# BMA253_Triaxial_Acceleration_Sensor.net
KiCad netlist of a schematic drawn in Altium Designer
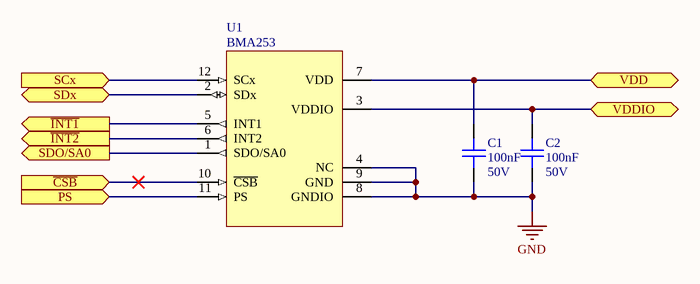
[diagram p0: BMA253_Triaxial_Acceleration_Sensor.SchDoc]

(export (version "E")
  (design (tool "Eeschema 10.0.6"))
  (components
    (comp (ref "C1")
      (value "CAP CER 0.1UF 50V X7R 0402")
      (footprint "C0402")
      (description "0.1µF ±10% 50V Ceramic Capacitor X7R 0402 (1005 Metric)")
      (fields
        (field (name "MANUFACTURER PART NUMBER") "CGA2B3X7R1H104K050BB")
        (field (name "MANUFACTURER") "TDK")
        (field (name "CAPACITANCE") "100nF")
        (field (name "VOLTAGE") "50V")
      )
      (libsource (lib "capacitors_smd") (part "CAP CER 0.1UF 50V X7R 0402"))
    )
    (comp (ref "C2")
      (value "CAP CER 0.1UF 50V X7R 0402")
      (footprint "C0402")
      (description "0.1µF ±10% 50V Ceramic Capacitor X7R 0402 (1005 Metric)")
      (fields
        (field (name "MANUFACTURER PART NUMBER") "CGA2B3X7R1H104K050BB")
        (field (name "MANUFACTURER") "TDK")
        (field (name "CAPACITANCE") "100nF")
        (field (name "VOLTAGE") "50V")
      )
      (libsource (lib "capacitors_smd") (part "CAP CER 0.1UF 50V X7R 0402"))
    )
    (comp (ref "U1")
      (value "BMA253")
      (footprint "LGA12C50P4X4_200X200X100")
      (description "Accelerometer X, Y, Z Axis ±2g, 4g, 8g, 16g 8Hz ~ 1kHz 12-LGA (2x2)")
      (fields (field (name "MANUFACTURER") "Bosch Sensortec"))
      (libsource (lib "BLDC_Motor_Driver") (part "IC BMA253 ACCEL 2-16G I2C/SPI 12LGA"))
    )
  )
  (nets
    (net (code "1") (name "/CSB") (class "Default")
      (node (ref "U1") (pin "10") (pinfunction "CSB_10") (pintype "input"))
    )
    (net (code "2") (name "/INT1") (class "Default")
      (node (ref "U1") (pin "5") (pinfunction "INT1_5") (pintype "output"))
    )
    (net (code "3") (name "/INT2") (class "Default")
      (node (ref "U1") (pin "6") (pinfunction "INT2_6") (pintype "output"))
    )
    (net (code "4") (name "/PS") (class "Default")
      (node (ref "U1") (pin "11") (pinfunction "PS_11") (pintype "input"))
    )
    (net (code "5") (name "/SCx") (class "Default")
      (node (ref "U1") (pin "12") (pinfunction "SCx_12") (pintype "input"))
    )
    (net (code "6") (name "/SDO{slash}SA0") (class "Default")
      (node (ref "U1") (pin "1") (pinfunction "SDO/SA0_1") (pintype "output"))
    )
    (net (code "7") (name "/SDx") (class "Default")
      (node (ref "U1") (pin "2") (pinfunction "SDx_2") (pintype "bidirectional"))
    )
    (net (code "8") (name "/VDD") (class "Default")
      (node (ref "C1") (pin "2") (pinfunction "2_2") (pintype "passive"))
      (node (ref "U1") (pin "7") (pinfunction "VDD_7") (pintype "power_in"))
    )
    (net (code "9") (name "/VDDIO") (class "Default")
      (node (ref "C2") (pin "1") (pinfunction "1_1") (pintype "passive"))
      (node (ref "U1") (pin "3") (pinfunction "VDDIO_3") (pintype "power_in"))
    )
    (net (code "10") (name "GND") (class "Default")
      (node (ref "C1") (pin "1") (pinfunction "1_1") (pintype "passive"))
      (node (ref "C2") (pin "2") (pinfunction "2_2") (pintype "passive"))
      (node (ref "U1") (pin "4") (pinfunction "NC_4") (pintype "passive"))
      (node (ref "U1") (pin "8") (pinfunction "GNDIO_8") (pintype "power_in"))
      (node (ref "U1") (pin "9") (pinfunction "GND_9") (pintype "power_in"))
    )
  )
)
